# FE_Channel.net
KiCad netlist of a schematic drawn in Altium Designer
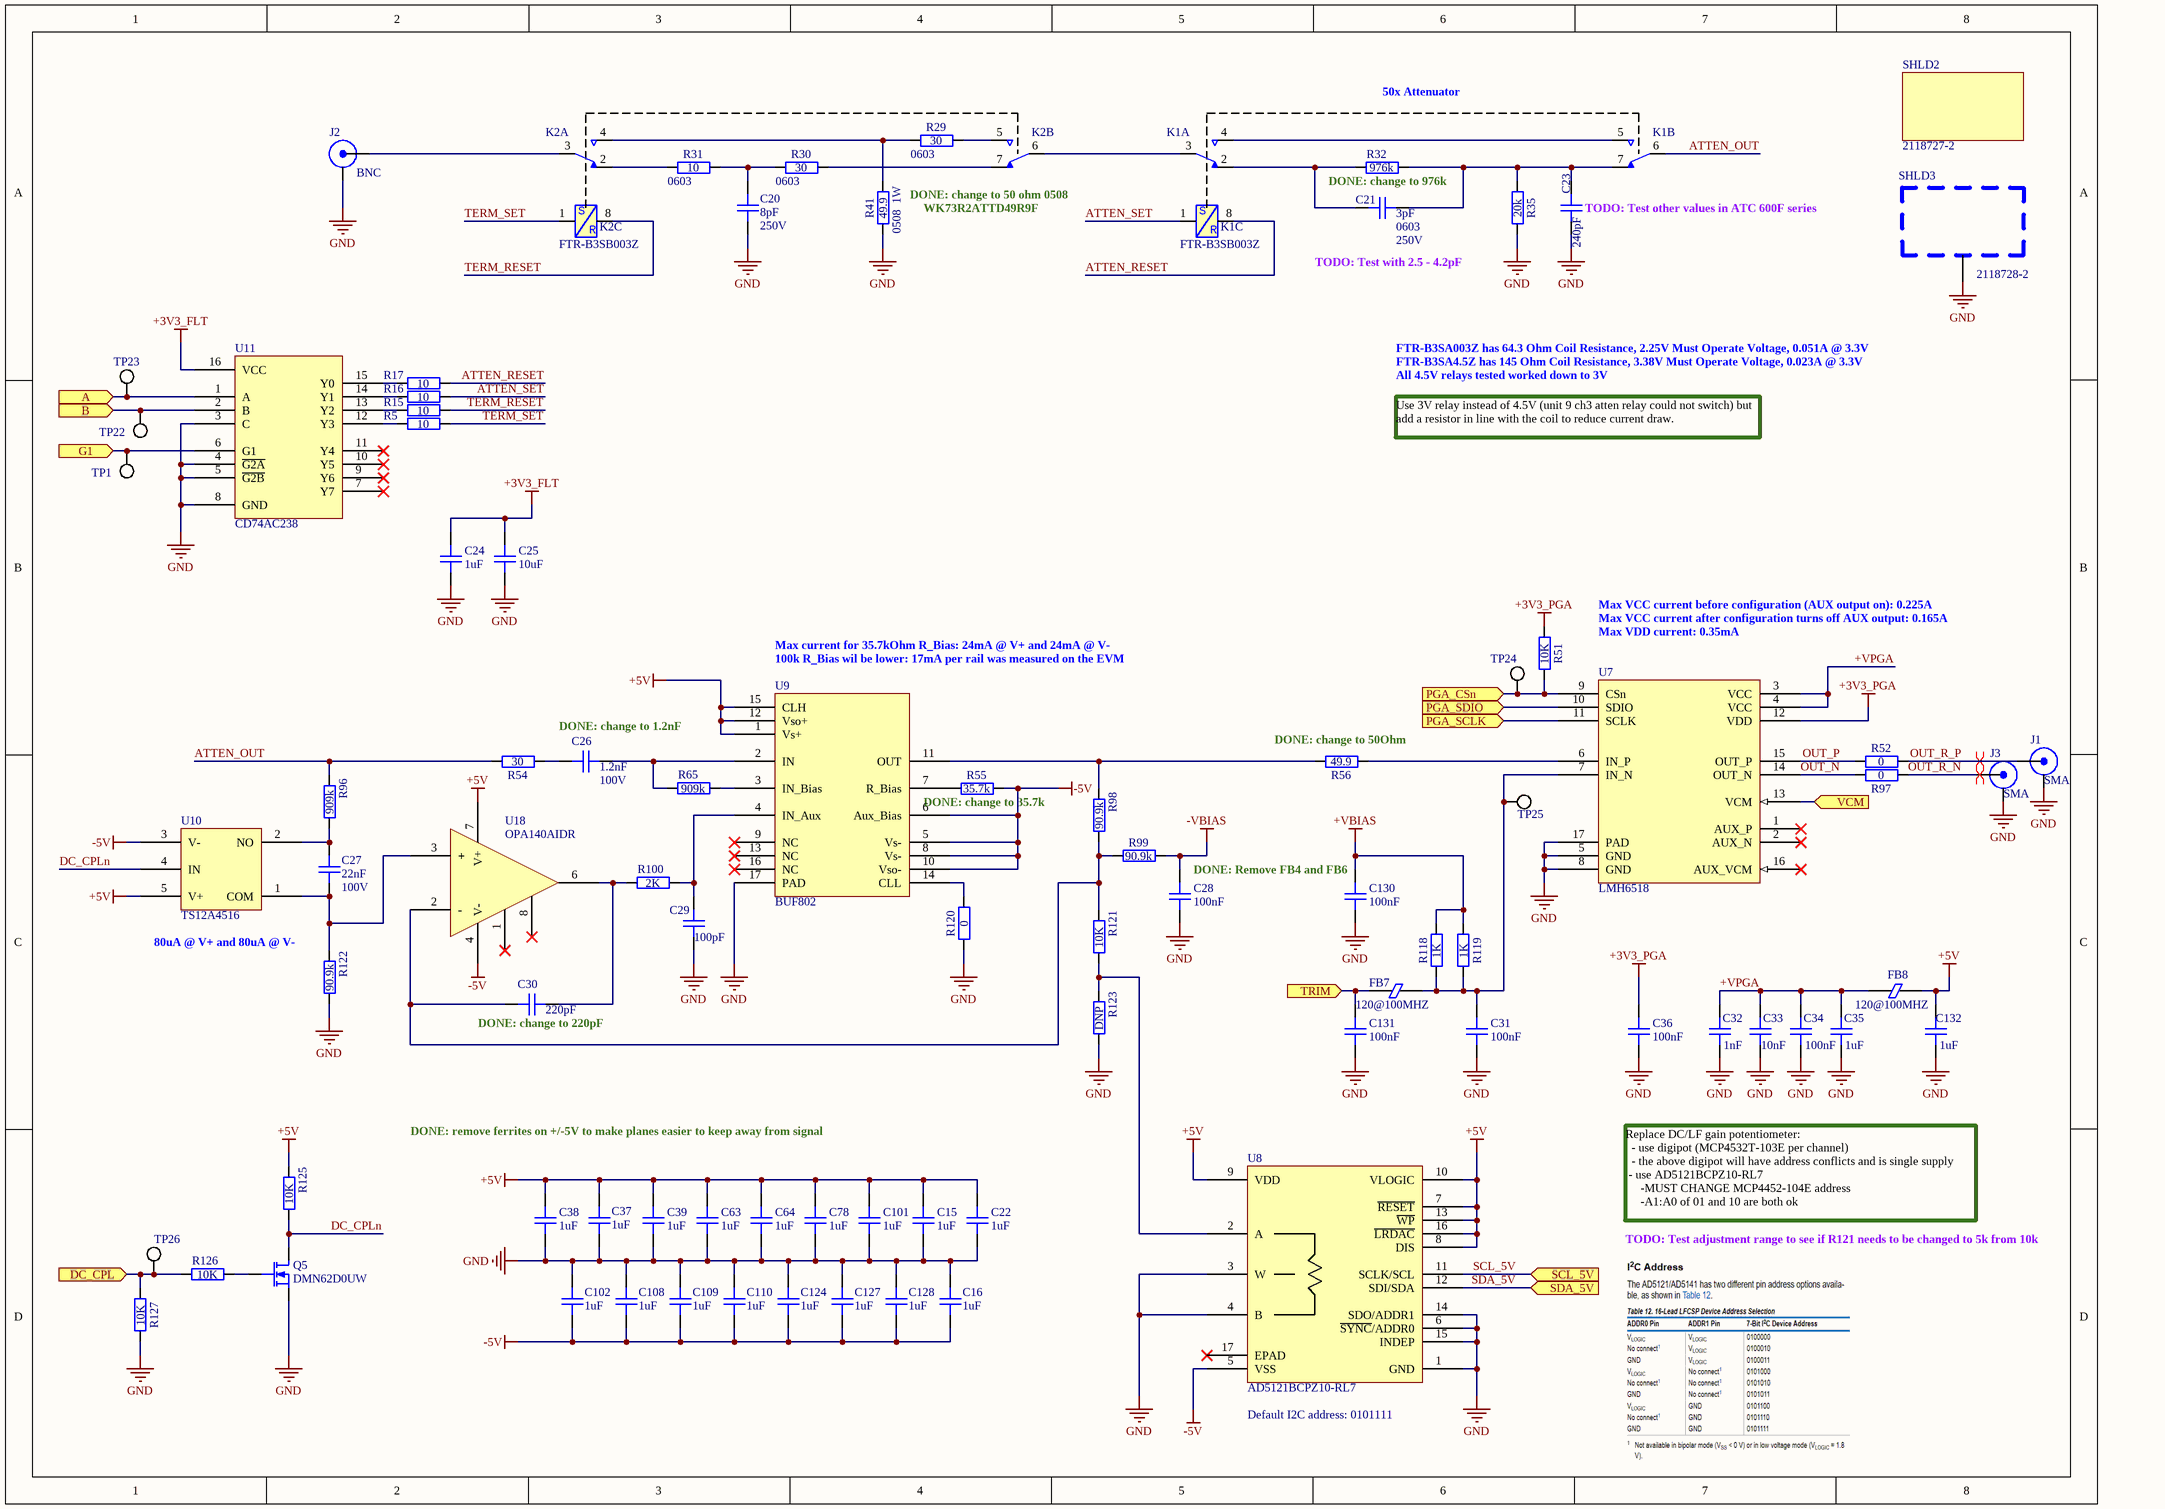
[diagram p0: FE_Channel.SchDoc]

(export (version "E")
  (design (tool "Eeschema 10.0.6"))
  (components
    (comp (ref "C15")
      (value "1uF")
      (footprint "GEN_C_0402")
      (fields
        (field (name "MANUFACTURER") "Murata")
        (field (name "MANUFACTURER PART NUMBER") "GRM155R61E105KA12D")
      )
      (libsource (lib "DSO") (part "CAP 1uF 25V X5R 0402"))
    )
    (comp (ref "C16")
      (value "1uF")
      (footprint "GEN_C_0402")
      (fields
        (field (name "MANUFACTURER") "Murata")
        (field (name "MANUFACTURER PART NUMBER") "GRM155R61E105KA12D")
      )
      (libsource (lib "DSO") (part "CAP 1uF 25V X5R 0402"))
    )
    (comp (ref "C20")
      (value "8pF")
      (footprint "GEN_C_0603")
      (fields
        (field (name "MANUFACTURER") "KEMET")
        (field (name "MANUFACTURER PART NUMBER") "CBR06C809BAGAC")
        (field (name "VOLTAGE RATING") "250V")
      )
      (libsource (lib "DSO") (part "CAP 8pF 250V C0G 0603"))
    )
    (comp (ref "C21")
      (value "3pF")
      (footprint "GEN_C_0603")
      (fields
        (field (name "PACKAGE") "0603")
        (field (name "VOLTAGE RATING") "250V")
        (field (name "MANUFACTURER") "KEMET")
        (field (name "MANUFACTURER PART NUMBER") "CBR06C309BAGAC")
      )
      (libsource (lib "DSO") (part "CAP 3pF 250V C0G 0603"))
    )
    (comp (ref "C22")
      (value "1uF")
      (footprint "GEN_C_0402")
      (fields
        (field (name "MANUFACTURER") "Murata")
        (field (name "MANUFACTURER PART NUMBER") "GRM155R61E105KA12D")
      )
      (libsource (lib "DSO") (part "CAP 1uF 25V X5R 0402"))
    )
    (comp (ref "C23")
      (value "240pF")
      (footprint "GEN_C_0805")
      (fields
        (field (name "MANUFACTURER") "Kyocera AVX")
        (field (name "MANUFACTURER PART NUMBER") "600F241FT250XT")
      )
      (libsource (lib "DSO") (part "CAP 240pF 250V C0G 0805"))
    )
    (comp (ref "C24")
      (value "1uF")
      (footprint "GEN_C_0402")
      (fields
        (field (name "MANUFACTURER") "Murata")
        (field (name "MANUFACTURER PART NUMBER") "GRM155R61E105KA12D")
      )
      (libsource (lib "DSO") (part "CAP 1uF 25V X5R 0402"))
    )
    (comp (ref "C25")
      (value "10uF")
      (footprint "GEN_C_0603")
      (fields
        (field (name "HOUSE PART NUMBER") "C-10uF-0603-002")
        (field (name "MANUFACTURER") "Murata")
        (field (name "MANUFACTURER PART NUMBER") "GRM188R61A106ME69D")
      )
      (libsource (lib "DSO") (part "CAP 10uF 10V X5R 0603"))
    )
    (comp (ref "C26")
      (value "1.2nF")
      (footprint "GEN_C_0603")
      (fields
        (field (name "VOLTAGE RATING") "100V")
        (field (name "MANUFACTURER") "Murata")
        (field (name "MANUFACTURER PART NUMBER") "GCM1885C2A122FA16D")
      )
      (libsource (lib "DSO") (part "CAP 1.2nF 100V C0G 0603"))
    )
    (comp (ref "C27")
      (value "22nF")
      (footprint "GEN_C_0603")
      (fields
        (field (name "VOLTAGE RATING") "100V")
        (field (name "MANUFACTURER") "Murata")
        (field (name "MANUFACTURER PART NUMBER") "GCM188R72A223KA37D")
      )
      (libsource (lib "DSO") (part "CAP 22nF 100V X7R 0603"))
    )
    (comp (ref "C28")
      (value "100nF")
      (footprint "GEN_C_0402")
      (fields
        (field (name "HOUSE PART NUMBER") "C-100nF-0402-002")
        (field (name "MANUFACTURER") "Murata")
        (field (name "MANUFACTURER PART NUMBER") "GCM155R71C104KA55D")
      )
      (libsource (lib "DSO") (part "CAP 100nF 16V X7R 0402"))
    )
    (comp (ref "C29")
      (value "100pF")
      (footprint "GEN_C_0402")
      (fields
        (field (name "MANUFACTURER") "Murata")
        (field (name "MANUFACTURER PART NUMBER") "GCM1555C1H101FA16D")
      )
      (libsource (lib "DSO") (part "CAP 100pF 50V C0G 0402"))
    )
    (comp (ref "C30")
      (value "220pF")
      (footprint "GEN_C_0402")
      (fields
        (field (name "MANUFACTURER") "Murata")
        (field (name "MANUFACTURER PART NUMBER") "GCM1555C1H221FA16J")
      )
      (libsource (lib "DSO") (part "CAP 220pF 50V C0G 0402"))
    )
    (comp (ref "C31")
      (value "100nF")
      (footprint "GEN_C_0402")
      (fields
        (field (name "HOUSE PART NUMBER") "C-100nF-0402-002")
        (field (name "MANUFACTURER") "Murata")
        (field (name "MANUFACTURER PART NUMBER") "GCM155R71C104KA55D")
      )
      (libsource (lib "DSO") (part "CAP 100nF 16V X7R 0402"))
    )
    (comp (ref "C32")
      (value "1nF")
      (footprint "GEN_C_0402")
      (fields
        (field (name "MANUFACTURER") "Murata")
        (field (name "MANUFACTURER PART NUMBER") "GRM1555C1H102FA01D")
      )
      (libsource (lib "DSO") (part "CAP 1nF 50V C0G 0402"))
    )
    (comp (ref "C33")
      (value "10nF")
      (footprint "GEN_C_0402")
      (fields
        (field (name "HOUSE PART NUMBER") "C-10nF-0402-002")
        (field (name "MANUFACTURER") "Murata")
        (field (name "MANUFACTURER PART NUMBER") "GRM155R71H103KA88J")
      )
      (libsource (lib "DSO") (part "CAP 10nF 50V X7R 0402"))
    )
    (comp (ref "C34")
      (value "100nF")
      (footprint "GEN_C_0402")
      (fields
        (field (name "HOUSE PART NUMBER") "C-100nF-0402-002")
        (field (name "MANUFACTURER") "Murata")
        (field (name "MANUFACTURER PART NUMBER") "GCM155R71C104KA55D")
      )
      (libsource (lib "DSO") (part "CAP 100nF 16V X7R 0402"))
    )
    (comp (ref "C35")
      (value "1uF")
      (footprint "GEN_C_0402")
      (fields
        (field (name "MANUFACTURER") "Murata")
        (field (name "MANUFACTURER PART NUMBER") "GRM155R61E105KA12D")
      )
      (libsource (lib "DSO") (part "CAP 1uF 25V X5R 0402"))
    )
    (comp (ref "C36")
      (value "100nF")
      (footprint "GEN_C_0402")
      (fields
        (field (name "HOUSE PART NUMBER") "C-100nF-0402-002")
        (field (name "MANUFACTURER") "Murata")
        (field (name "MANUFACTURER PART NUMBER") "GCM155R71C104KA55D")
      )
      (libsource (lib "DSO") (part "CAP 100nF 16V X7R 0402"))
    )
    (comp (ref "C37")
      (value "1uF")
      (footprint "GEN_C_0402")
      (fields
        (field (name "MANUFACTURER") "Murata")
        (field (name "MANUFACTURER PART NUMBER") "GRM155R61E105KA12D")
      )
      (libsource (lib "DSO") (part "CAP 1uF 25V X5R 0402"))
    )
    (comp (ref "C38")
      (value "1uF")
      (footprint "GEN_C_0402")
      (fields
        (field (name "MANUFACTURER") "Murata")
        (field (name "MANUFACTURER PART NUMBER") "GRM155R61E105KA12D")
      )
      (libsource (lib "DSO") (part "CAP 1uF 25V X5R 0402"))
    )
    (comp (ref "C39")
      (value "1uF")
      (footprint "GEN_C_0402")
      (fields
        (field (name "MANUFACTURER") "Murata")
        (field (name "MANUFACTURER PART NUMBER") "GRM155R61E105KA12D")
      )
      (libsource (lib "DSO") (part "CAP 1uF 25V X5R 0402"))
    )
    (comp (ref "C63")
      (value "1uF")
      (footprint "GEN_C_0402")
      (fields
        (field (name "MANUFACTURER") "Murata")
        (field (name "MANUFACTURER PART NUMBER") "GRM155R61E105KA12D")
      )
      (libsource (lib "DSO") (part "CAP 1uF 25V X5R 0402"))
    )
    (comp (ref "C64")
      (value "1uF")
      (footprint "GEN_C_0402")
      (fields
        (field (name "MANUFACTURER") "Murata")
        (field (name "MANUFACTURER PART NUMBER") "GRM155R61E105KA12D")
      )
      (libsource (lib "DSO") (part "CAP 1uF 25V X5R 0402"))
    )
    (comp (ref "C78")
      (value "1uF")
      (footprint "GEN_C_0402")
      (fields
        (field (name "MANUFACTURER") "Murata")
        (field (name "MANUFACTURER PART NUMBER") "GRM155R61E105KA12D")
      )
      (libsource (lib "DSO") (part "CAP 1uF 25V X5R 0402"))
    )
    (comp (ref "C101")
      (value "1uF")
      (footprint "GEN_C_0402")
      (fields
        (field (name "MANUFACTURER") "Murata")
        (field (name "MANUFACTURER PART NUMBER") "GRM155R61E105KA12D")
      )
      (libsource (lib "DSO") (part "CAP 1uF 25V X5R 0402"))
    )
    (comp (ref "C102")
      (value "1uF")
      (footprint "GEN_C_0402")
      (fields
        (field (name "MANUFACTURER") "Murata")
        (field (name "MANUFACTURER PART NUMBER") "GRM155R61E105KA12D")
      )
      (libsource (lib "DSO") (part "CAP 1uF 25V X5R 0402"))
    )
    (comp (ref "C108")
      (value "1uF")
      (footprint "GEN_C_0402")
      (fields
        (field (name "MANUFACTURER") "Murata")
        (field (name "MANUFACTURER PART NUMBER") "GRM155R61E105KA12D")
      )
      (libsource (lib "DSO") (part "CAP 1uF 25V X5R 0402"))
    )
    (comp (ref "C109")
      (value "1uF")
      (footprint "GEN_C_0402")
      (fields
        (field (name "MANUFACTURER") "Murata")
        (field (name "MANUFACTURER PART NUMBER") "GRM155R61E105KA12D")
      )
      (libsource (lib "DSO") (part "CAP 1uF 25V X5R 0402"))
    )
    (comp (ref "C110")
      (value "1uF")
      (footprint "GEN_C_0402")
      (fields
        (field (name "MANUFACTURER") "Murata")
        (field (name "MANUFACTURER PART NUMBER") "GRM155R61E105KA12D")
      )
      (libsource (lib "DSO") (part "CAP 1uF 25V X5R 0402"))
    )
    (comp (ref "C124")
      (value "1uF")
      (footprint "GEN_C_0402")
      (fields
        (field (name "MANUFACTURER") "Murata")
        (field (name "MANUFACTURER PART NUMBER") "GRM155R61E105KA12D")
      )
      (libsource (lib "DSO") (part "CAP 1uF 25V X5R 0402"))
    )
    (comp (ref "C127")
      (value "1uF")
      (footprint "GEN_C_0402")
      (fields
        (field (name "MANUFACTURER") "Murata")
        (field (name "MANUFACTURER PART NUMBER") "GRM155R61E105KA12D")
      )
      (libsource (lib "DSO") (part "CAP 1uF 25V X5R 0402"))
    )
    (comp (ref "C128")
      (value "1uF")
      (footprint "GEN_C_0402")
      (fields
        (field (name "MANUFACTURER") "Murata")
        (field (name "MANUFACTURER PART NUMBER") "GRM155R61E105KA12D")
      )
      (libsource (lib "DSO") (part "CAP 1uF 25V X5R 0402"))
    )
    (comp (ref "C130")
      (value "100nF")
      (footprint "GEN_C_0402")
      (fields
        (field (name "HOUSE PART NUMBER") "C-100nF-0402-002")
        (field (name "MANUFACTURER") "Murata")
        (field (name "MANUFACTURER PART NUMBER") "GCM155R71C104KA55D")
      )
      (libsource (lib "DSO") (part "CAP 100nF 16V X7R 0402"))
    )
    (comp (ref "C131")
      (value "100nF")
      (footprint "GEN_C_0402")
      (fields
        (field (name "HOUSE PART NUMBER") "C-100nF-0402-002")
        (field (name "MANUFACTURER") "Murata")
        (field (name "MANUFACTURER PART NUMBER") "GCM155R71C104KA55D")
      )
      (libsource (lib "DSO") (part "CAP 100nF 16V X7R 0402"))
    )
    (comp (ref "C132")
      (value "1uF")
      (footprint "GEN_C_0402")
      (fields
        (field (name "MANUFACTURER") "Murata")
        (field (name "MANUFACTURER PART NUMBER") "GRM155R61E105KA12D")
      )
      (libsource (lib "DSO") (part "CAP 1uF 25V X5R 0402"))
    )
    (comp (ref "FB7")
      (value "120@100MHZ")
      (footprint "GEN_R_0402")
      (fields (field (name "HOUSE PART NUMBER") "BLM15PX121SN1D") (field (name "MANUFACTURER") "Murata"))
      (libsource (lib "DSO") (part "FERRITE BEAD 120 OHM 0402"))
    )
    (comp (ref "FB8")
      (value "120@100MHZ")
      (footprint "GEN_R_0402")
      (fields (field (name "HOUSE PART NUMBER") "BLM15PX121SN1D") (field (name "MANUFACTURER") "Murata"))
      (libsource (lib "DSO") (part "FERRITE BEAD 120 OHM 0402"))
    )
    (comp (ref "J1")
      (value "SMA")
      (footprint "MOL_0733910083")
      (fields (field (name "MANUFACTURER") "Molex") (field (name "MANUFACTURER PART NUMBER") "73100-0105"))
      (libsource (lib "DSO") (part "SMA JACK R/A"))
    )
    (comp (ref "J2")
      (value "BNC")
      (footprint "MOL_0731000105")
      (fields (field (name "MANUFACTURER") "Molex") (field (name "MANUFACTURER PART NUMBER") "73100-0105"))
      (libsource (lib "DSO") (part "BNC JACK R/A"))
    )
    (comp (ref "J3")
      (value "SMA")
      (footprint "MOL_0733910083")
      (fields (field (name "MANUFACTURER") "Molex") (field (name "MANUFACTURER PART NUMBER") "73100-0105"))
      (libsource (lib "DSO") (part "SMA JACK R/A"))
    )
    (comp (ref "K1")
      (value "FTR-B3SB003Z")
      (footprint "FUJ_FTR-B3SA")
      (fields (field (name "MANUFACTURER") "Fujitsu"))
      (libsource (lib "") (part "RELAY DPDT-NO FTR-B3SB003Z_1"))
    )
    (comp (ref "K2")
      (value "FTR-B3SB003Z")
      (footprint "FUJ_FTR-B3SA")
      (fields (field (name "MANUFACTURER") "Fujitsu"))
      (libsource (lib "DSO") (part "RELAY DPDT-NO FTR-B3SB003Z"))
    )
    (comp (ref "Q5")
      (value "DMN62D0UW")
      (footprint "GEN_SOT_323")
      (fields (field (name "HOUSE PART NUMBER") "DMN62D0UW-7") (field (name "MANUFACTURER") "Diodes"))
      (libsource (lib "DSO") (part "NMOS DMN62D0UW"))
    )
    (comp (ref "R5")
      (value "10")
      (footprint "GEN_R_0603")
      (fields
        (field (name "TOLERANCE") "1%")
        (field (name "MANUFACTURER") "KOA Speer")
        (field (name "MANUFACTURER PART NUMBER") "SG73P1JTTD10R0F")
      )
      (libsource (lib "DSO") (part "RES 10 OHM 1% 1/3W 0603"))
    )
    (comp (ref "R15")
      (value "10")
      (footprint "GEN_R_0603")
      (fields
        (field (name "TOLERANCE") "1%")
        (field (name "MANUFACTURER") "KOA Speer")
        (field (name "MANUFACTURER PART NUMBER") "SG73P1JTTD10R0F")
      )
      (libsource (lib "DSO") (part "RES 10 OHM 1% 1/3W 0603"))
    )
    (comp (ref "R16")
      (value "10")
      (footprint "GEN_R_0603")
      (fields
        (field (name "TOLERANCE") "1%")
        (field (name "MANUFACTURER") "KOA Speer")
        (field (name "MANUFACTURER PART NUMBER") "SG73P1JTTD10R0F")
      )
      (libsource (lib "DSO") (part "RES 10 OHM 1% 1/3W 0603"))
    )
    (comp (ref "R17")
      (value "10")
      (footprint "GEN_R_0603")
      (fields
        (field (name "TOLERANCE") "1%")
        (field (name "MANUFACTURER") "KOA Speer")
        (field (name "MANUFACTURER PART NUMBER") "SG73P1JTTD10R0F")
      )
      (libsource (lib "DSO") (part "RES 10 OHM 1% 1/3W 0603"))
    )
    (comp (ref "R29")
      (value "30")
      (footprint "GEN_R_0603")
      (fields
        (field (name "TOLERANCE") "1%")
        (field (name "PACKAGE") "0603")
        (field (name "MANUFACTURER") "KOA Speer")
        (field (name "MANUFACTURER PART NUMBER") "SG73P1JTTD30R0F")
      )
      (libsource (lib "DSO") (part "RES 30 OHM 1% 1/3W 0603"))
    )
    (comp (ref "R30")
      (value "30")
      (footprint "GEN_R_0603")
      (fields
        (field (name "TOLERANCE") "1%")
        (field (name "PACKAGE") "0603")
        (field (name "MANUFACTURER") "KOA Speer")
        (field (name "MANUFACTURER PART NUMBER") "SG73P1JTTD30R0F")
      )
      (libsource (lib "DSO") (part "RES 30 OHM 1% 1/3W 0603"))
    )
    (comp (ref "R31")
      (value "10")
      (footprint "GEN_R_0603")
      (fields
        (field (name "TOLERANCE") "1%")
        (field (name "PACKAGE") "0603")
        (field (name "MANUFACTURER") "KOA Speer")
        (field (name "MANUFACTURER PART NUMBER") "SG73P1JTTD10R0F")
      )
      (libsource (lib "") (part "RES 10 OHM 1% 1/3W 0603_1"))
    )
    (comp (ref "R32")
      (value "976k")
      (footprint "GEN_R_0603")
      (fields
        (field (name "MANUFACTURER") "KOA Speer")
        (field (name "MANUFACTURER PART NUMBER") "RK73H1JTTD9763F")
        (field (name "TOLERANCE") "1%")
      )
      (libsource (lib "DSO") (part "RES 976k OHM 1% 1/10W 0603"))
    )
    (comp (ref "R35")
      (value "20k")
      (footprint "GEN_R_0402")
      (fields
        (field (name "TOLERANCE") "1%")
        (field (name "MANUFACTURER") "Yageo")
        (field (name "MANUFACTURER PART NUMBER") "RC0402FR-0720KL")
      )
      (libsource (lib "DSO") (part "RES 20K OHM 1% 1/16W 0402"))
    )
    (comp (ref "R41")
      (value "49.9")
      (footprint "GEN_R_0508")
      (fields
        (field (name "TOLERANCE") "1%")
        (field (name "PACKAGE") "0508")
        (field (name "MANUFACTURER") "KOA Speer")
        (field (name "MANUFACTURER PART NUMBER") "WK73R2ATTD49R9F")
        (field (name "POWER RATING") "1W")
      )
      (libsource (lib "DSO") (part "RES 49.9 OHM 1% 1W 0508"))
    )
    (comp (ref "R51")
      (value "10K")
      (footprint "GEN_R_0402")
      (fields
        (field (name "TOLERANCE") "1%")
        (field (name "MANUFACTURER") "Panasonic")
        (field (name "MANUFACTURER PART NUMBER") "ERJ-2RKF1002X")
      )
      (libsource (lib "DSO") (part "RES 10K OHM 1% 1/10W 0402"))
    )
    (comp (ref "R52")
      (value "0")
      (footprint "GEN_R_0402")
      (fields
        (field (name "MANUFACTURER") "Yageo")
        (field (name "MANUFACTURER PART NUMBER") "RC0402JR-070RL")
      )
      (libsource (lib "DSO") (part "RES 0 OHM 1/16W 0402"))
    )
    (comp (ref "R54")
      (value "30")
      (footprint "GEN_R_0603")
      (fields
        (field (name "TOLERANCE") "1%")
        (field (name "MANUFACTURER") "KOA Speer")
        (field (name "MANUFACTURER PART NUMBER") "SG73P1JTTD30R0F")
      )
      (libsource (lib "DSO") (part "RES 30 OHM 1% 1/3W 0603"))
    )
    (comp (ref "R55")
      (value "35.7k")
      (footprint "GEN_R_0402")
      (fields
        (field (name "TOLERANCE") "1%")
        (field (name "MANUFACTURER") "Yageo")
        (field (name "MANUFACTURER PART NUMBER") "RC0402FR-0735K7L")
      )
      (libsource (lib "DSO") (part "RES 35.7K OHM 1% 1/16W 0402"))
    )
    (comp (ref "R56")
      (value "49.9")
      (footprint "GEN_R_0402")
      (fields
        (field (name "MANUFACTURER") "Yageo")
        (field (name "MANUFACTURER PART NUMBER") "RC0402FR-0749R9L")
        (field (name "TOLERANCE") "1%")
      )
      (libsource (lib "DSO") (part "RES 49.9 OHM 1% 1/10W 0402"))
    )
    (comp (ref "R65")
      (value "909k")
      (footprint "GEN_R_0402")
      (fields
        (field (name "TOLERANCE") "1%")
        (field (name "MANUFACTURER") "Yageo")
        (field (name "MANUFACTURER PART NUMBER") "RC0402FR-07909KL")
      )
      (libsource (lib "DSO") (part "RES 909K OHM 1% 1/16W 0402"))
    )
    (comp (ref "R96")
      (value "909k")
      (footprint "GEN_R_0402")
      (fields
        (field (name "TOLERANCE") "1%")
        (field (name "MANUFACTURER") "Yageo")
        (field (name "MANUFACTURER PART NUMBER") "RC0402FR-07909KL")
      )
      (libsource (lib "") (part "RES 909K OHM 1% 1/16W 0402_1"))
    )
    (comp (ref "R97")
      (value "0")
      (footprint "GEN_R_0402")
      (fields
        (field (name "MANUFACTURER") "Yageo")
        (field (name "MANUFACTURER PART NUMBER") "RC0402JR-070RL")
      )
      (libsource (lib "DSO") (part "RES 0 OHM 1/16W 0402"))
    )
    (comp (ref "R98")
      (value "90.9k")
      (footprint "GEN_R_0402")
      (fields
        (field (name "TOLERANCE") "1%")
        (field (name "MANUFACTURER") "Yageo")
        (field (name "MANUFACTURER PART NUMBER") "RC0402FR-0790K9L")
      )
      (libsource (lib "DSO") (part "RES 90.9K OHM 1% 1/16W 0402"))
    )
    (comp (ref "R99")
      (value "90.9k")
      (footprint "GEN_R_0402")
      (fields
        (field (name "TOLERANCE") "1%")
        (field (name "MANUFACTURER") "Yageo")
        (field (name "MANUFACTURER PART NUMBER") "RC0402FR-0790K9L")
      )
      (libsource (lib "") (part "RES 90.9K OHM 1% 1/16W 0402_1"))
    )
    (comp (ref "R100")
      (value "2K")
      (footprint "GEN_R_0402")
      (fields
        (field (name "TOLERANCE") "1%")
        (field (name "MANUFACTURER") "Yageo")
        (field (name "MANUFACTURER PART NUMBER") "RC0402FR-072KL")
      )
      (libsource (lib "DSO") (part "RES 2K OHM 1% 1/16W 0402"))
    )
    (comp (ref "R118")
      (value "1K")
      (footprint "GEN_R_0402")
      (fields
        (field (name "TOLERANCE") "1%")
        (field (name "HOUSE PART NUMBER") "R-1K-0402-1%-001")
        (field (name "MANUFACTURER") "Yageo")
      )
      (libsource (lib "DSO") (part "RES 1K OHM 1% 1/10W 0402"))
    )
    (comp (ref "R119")
      (value "1K")
      (footprint "GEN_R_0402")
      (fields
        (field (name "TOLERANCE") "1%")
        (field (name "HOUSE PART NUMBER") "R-1K-0402-1%-001")
        (field (name "MANUFACTURER") "Yageo")
      )
      (libsource (lib "") (part "RES 1K OHM 1% 1/10W 0402_1"))
    )
    (comp (ref "R120")
      (value "0")
      (footprint "GEN_R_0402")
      (fields
        (field (name "MANUFACTURER") "Yageo")
        (field (name "MANUFACTURER PART NUMBER") "RC0402JR-070RL")
      )
      (libsource (lib "") (part "RES 0 OHM 1/16W 0402_1"))
    )
    (comp (ref "R121")
      (value "10K")
      (footprint "GEN_R_0402")
      (fields
        (field (name "TOLERANCE") "1%")
        (field (name "MANUFACTURER") "Panasonic")
        (field (name "MANUFACTURER PART NUMBER") "ERJ-2RKF1002X")
      )
      (libsource (lib "DSO") (part "RES 10K OHM 1% 1/10W 0402"))
    )
    (comp (ref "R122")
      (value "90.9k")
      (footprint "GEN_R_0402")
      (fields
        (field (name "TOLERANCE") "1%")
        (field (name "MANUFACTURER") "Yageo")
        (field (name "MANUFACTURER PART NUMBER") "RC0402FR-0790K9L")
      )
      (libsource (lib "DSO") (part "RES 90.9K OHM 1% 1/16W 0402"))
    )
    (comp (ref "R123")
      (value "DNP")
      (footprint "GEN_R_0402")
      (fields (field (name "TOLERANCE") "1%"))
      (libsource (lib "DSO") (part "RES DNP 0402"))
    )
    (comp (ref "R125")
      (value "10K")
      (footprint "GEN_R_0402")
      (fields
        (field (name "TOLERANCE") "1%")
        (field (name "MANUFACTURER") "Panasonic")
        (field (name "MANUFACTURER PART NUMBER") "ERJ-2RKF1002X")
      )
      (libsource (lib "DSO") (part "RES 10K OHM 1% 1/10W 0402"))
    )
    (comp (ref "R126")
      (value "10K")
      (footprint "GEN_R_0402")
      (fields
        (field (name "TOLERANCE") "1%")
        (field (name "MANUFACTURER") "Panasonic")
        (field (name "MANUFACTURER PART NUMBER") "ERJ-2RKF1002X")
      )
      (libsource (lib "") (part "RES 10K OHM 1% 1/10W 0402_1"))
    )
    (comp (ref "R127")
      (value "10K")
      (footprint "GEN_R_0402")
      (fields
        (field (name "TOLERANCE") "1%")
        (field (name "MANUFACTURER") "Panasonic")
        (field (name "MANUFACTURER PART NUMBER") "ERJ-2RKF1002X")
      )
      (libsource (lib "") (part "RES 10K OHM 1% 1/10W 0402_2"))
    )
    (comp (ref "SHLD2")
      (value "2118727-2")
      (fields (field (name "MANUFACTURER") "TE Connectivity AMP"))
      (libsource (lib "DSO") (part "SHIELD 2118727-2"))
    )
    (comp (ref "SHLD3")
      (value "2118728-2")
      (footprint "TE_2118728-2")
      (fields (field (name "MANUFACTURER") "TE Connectivity"))
      (libsource (lib "DSO") (part "SHIELD 2118728-2"))
    )
    (comp (ref "TP1") (value "PCB") (footprint "GEN_TP_PCB") (libsource (lib "DSO") (part "TP PCB 1mm")))
    (comp (ref "TP22") (value "PCB") (footprint "GEN_TP_PCB") (libsource (lib "DSO") (part "TP PCB 1mm")))
    (comp (ref "TP23") (value "PCB") (footprint "GEN_TP_PCB") (libsource (lib "DSO") (part "TP PCB 1mm")))
    (comp (ref "TP24") (value "PCB") (footprint "GEN_TP_PCB") (libsource (lib "DSO") (part "TP PCB 1mm")))
    (comp (ref "TP25") (value "PCB") (footprint "GEN_TP_PCB") (libsource (lib "DSO") (part "TP PCB 1mm")))
    (comp (ref "TP26") (value "PCB") (footprint "GEN_TP_PCB") (libsource (lib "DSO") (part "TP PCB 1mm")))
    (comp (ref "U7")
      (value "LMH6518")
      (footprint "TI_WQFN_RGH0016A")
      (fields
        (field (name "MANUFACTURER") "Texas Instruments")
        (field (name "MANUFACTURER PART NUMBER") "LMH6518SQE/NOPB")
      )
      (libsource (lib "DSO") (part "IC PGA LMH6518"))
    )
    (comp (ref "U8")
      (value "AD5121BCPZ10-RL7")
      (footprint "AD_QFN16_CP-16-22")
      (fields (field (name "MANUFACTURER") "Analog Devices"))
      (libsource (lib "DSO") (part "IC DIGIPOT SINGLE AD5121BCPZ10-RL7"))
    )
    (comp (ref "U9")
      (value "BUF802")
      (footprint "TI_VQFN_RGT0016C")
      (fields
        (field (name "MANUFACTURER") "Texas Instruments")
        (field (name "MANUFACTURER PART NUMBER") "BUF802IRGTR")
      )
      (libsource (lib "DSO") (part "IC BUFFER AMP BUF802"))
    )
    (comp (ref "U10")
      (value "TS12A4516")
      (footprint "GEN_SOT23_5_950_2900X1600X1450")
      (fields
        (field (name "MANUFACTURER") "Texas Instruments")
        (field (name "MANUFACTURER PART NUMBER") "TS12A4516DBVR")
      )
      (libsource (lib "DSO") (part "IC SWITCH SPST TS12A4516DBVR"))
    )
    (comp (ref "U11")
      (value "CD74AC238")
      (footprint "TI_TSSOP16_PW0016A")
      (fields
        (field (name "MANUFACTURER") "Texas Instruments")
        (field (name "HOUSE PART NUMBER") "CD74AC238PWR")
      )
      (libsource (lib "DSO") (part "IC Decoder CD74AC238"))
    )
    (comp (ref "U18")
      (value "OPA140AIDR")
      (footprint "TI_SOIC8_D0008A")
      (fields (field (name "MANUFACTURER") "Texas Instruments"))
      (libsource (lib "DSO") (part "IC OPAMP OPA140"))
    )
  )
  (nets
    (net (code "1") (name "+3V3_FLT") (class "Default")
      (node (ref "C24") (pin "2") (pinfunction "2_2") (pintype "passive"))
      (node (ref "C25") (pin "2") (pinfunction "2_2") (pintype "passive"))
      (node (ref "U11") (pin "16") (pinfunction "VCC_16") (pintype "passive"))
    )
    (net (code "2") (name "+3V3_PGA") (class "Default")
      (node (ref "C36") (pin "2") (pinfunction "2_2") (pintype "passive"))
      (node (ref "R51") (pin "2") (pinfunction "2_2") (pintype "passive"))
      (node (ref "U7") (pin "12") (pinfunction "VDD_12") (pintype "power_in"))
    )
    (net (code "3") (name "+5V") (class "Default")
      (node (ref "C101") (pin "2") (pinfunction "2_2") (pintype "passive"))
      (node (ref "C132") (pin "2") (pinfunction "2_2") (pintype "passive"))
      (node (ref "C15") (pin "2") (pinfunction "2_2") (pintype "passive"))
      (node (ref "C22") (pin "2") (pinfunction "2_2") (pintype "passive"))
      (node (ref "C37") (pin "2") (pinfunction "2_2") (pintype "passive"))
      (node (ref "C38") (pin "1") (pinfunction "1_1") (pintype "passive"))
      (node (ref "C39") (pin "1") (pinfunction "1_1") (pintype "passive"))
      (node (ref "C63") (pin "1") (pinfunction "1_1") (pintype "passive"))
      (node (ref "C64") (pin "2") (pinfunction "2_2") (pintype "passive"))
      (node (ref "C78") (pin "2") (pinfunction "2_2") (pintype "passive"))
      (node (ref "FB8") (pin "2") (pinfunction "2_2") (pintype "passive"))
      (node (ref "R125") (pin "2") (pinfunction "2_2") (pintype "passive"))
      (node (ref "U10") (pin "5") (pinfunction "V+_5") (pintype "passive"))
      (node (ref "U18") (pin "7") (pinfunction "V+_7") (pintype "passive"))
      (node (ref "U8") (pin "10") (pinfunction "VLOGIC_10") (pintype "passive"))
      (node (ref "U8") (pin "13") (pinfunction "~{WP}_13") (pintype "passive"))
      (node (ref "U8") (pin "16") (pinfunction "~{LRDAC}_16") (pintype "passive"))
      (node (ref "U8") (pin "7") (pinfunction "~{RESET}_7") (pintype "passive"))
      (node (ref "U8") (pin "8") (pinfunction "DIS_8") (pintype "passive"))
      (node (ref "U8") (pin "9") (pinfunction "VDD_9") (pintype "passive"))
      (node (ref "U9") (pin "1") (pinfunction "Vs+_1") (pintype "passive"))
      (node (ref "U9") (pin "12") (pinfunction "Vso+_12") (pintype "passive"))
      (node (ref "U9") (pin "15") (pinfunction "CLH_15") (pintype "passive"))
    )
    (net (code "4") (name "+VBIAS") (class "Default")
      (node (ref "C130") (pin "1") (pinfunction "1_1") (pintype "passive"))
      (node (ref "R118") (pin "2") (pinfunction "2_2") (pintype "passive"))
      (node (ref "R119") (pin "1") (pinfunction "1_1") (pintype "passive"))
    )
    (net (code "5") (name "-5V") (class "Default")
      (node (ref "C102") (pin "2") (pinfunction "2_2") (pintype "passive"))
      (node (ref "C108") (pin "2") (pinfunction "2_2") (pintype "passive"))
      (node (ref "C109") (pin "1") (pinfunction "1_1") (pintype "passive"))
      (node (ref "C110") (pin "1") (pinfunction "1_1") (pintype "passive"))
      (node (ref "C124") (pin "1") (pinfunction "1_1") (pintype "passive"))
      (node (ref "C127") (pin "2") (pinfunction "2_2") (pintype "passive"))
      (node (ref "C128") (pin "2") (pinfunction "2_2") (pintype "passive"))
      (node (ref "C16") (pin "2") (pinfunction "2_2") (pintype "passive"))
      (node (ref "R55") (pin "2") (pinfunction "2_2") (pintype "passive"))
      (node (ref "U10") (pin "3") (pinfunction "V-_3") (pintype "passive"))
      (node (ref "U18") (pin "4") (pinfunction "V-_4") (pintype "passive"))
      (node (ref "U8") (pin "5") (pinfunction "VSS_5") (pintype "passive"))
      (node (ref "U9") (pin "10") (pinfunction "Vso-_10") (pintype "passive"))
      (node (ref "U9") (pin "5") (pinfunction "Vs-_5") (pintype "passive"))
      (node (ref "U9") (pin "6") (pinfunction "Aux_Bias_6") (pintype "passive"))
      (node (ref "U9") (pin "8") (pinfunction "Vs-_8") (pintype "passive"))
    )
    (net (code "6") (name "-VBIAS") (class "Default")
      (node (ref "C28") (pin "1") (pinfunction "1_1") (pintype "passive"))
      (node (ref "R99") (pin "1") (pinfunction "1_1") (pintype "passive"))
    )
    (net (code "7") (name "/+VPGA") (class "Default")
      (node (ref "C32") (pin "2") (pinfunction "2_2") (pintype "passive"))
      (node (ref "C33") (pin "2") (pinfunction "2_2") (pintype "passive"))
      (node (ref "C34") (pin "2") (pinfunction "2_2") (pintype "passive"))
      (node (ref "C35") (pin "2") (pinfunction "2_2") (pintype "passive"))
      (node (ref "FB8") (pin "1") (pinfunction "1_1") (pintype "passive"))
      (node (ref "U7") (pin "3") (pinfunction "VCC_3") (pintype "power_in"))
      (node (ref "U7") (pin "4") (pinfunction "VCC_4") (pintype "power_in"))
    )
    (net (code "8") (name "/A") (class "Default")
      (node (ref "TP23") (pin "1") (pinfunction "1_1") (pintype "passive"))
      (node (ref "U11") (pin "1") (pinfunction "A_1") (pintype "passive"))
    )
    (net (code "9") (name "/ATTEN_OUT") (class "Default")
      (node (ref "K1") (pin "6") (pinfunction "6_6") (pintype "passive"))
      (node (ref "R54") (pin "1") (pinfunction "1_1") (pintype "passive"))
      (node (ref "R96") (pin "2") (pinfunction "2_2") (pintype "passive"))
    )
    (net (code "10") (name "/ATTEN_RESET") (class "Default")
      (node (ref "K1") (pin "8") (pinfunction "8_8") (pintype "passive"))
      (node (ref "R17") (pin "2") (pinfunction "2_2") (pintype "passive"))
    )
    (net (code "11") (name "/ATTEN_SET") (class "Default")
      (node (ref "K1") (pin "1") (pinfunction "1_1") (pintype "passive"))
      (node (ref "R16") (pin "2") (pinfunction "2_2") (pintype "passive"))
    )
    (net (code "12") (name "/B") (class "Default")
      (node (ref "TP22") (pin "1") (pinfunction "1_1") (pintype "passive"))
      (node (ref "U11") (pin "2") (pinfunction "B_2") (pintype "passive"))
    )
    (net (code "13") (name "/DC_CPL") (class "Default")
      (node (ref "R126") (pin "2") (pinfunction "2_2") (pintype "passive"))
      (node (ref "R127") (pin "2") (pinfunction "2_2") (pintype "passive"))
      (node (ref "TP26") (pin "1") (pinfunction "1_1") (pintype "passive"))
    )
    (net (code "14") (name "/DC_CPLn") (class "Default")
      (node (ref "Q5") (pin "1") (pinfunction "D_1") (pintype "passive"))
      (node (ref "R125") (pin "1") (pinfunction "1_1") (pintype "passive"))
      (node (ref "U10") (pin "4") (pinfunction "IN_4") (pintype "passive"))
    )
    (net (code "15") (name "/G1") (class "Default")
      (node (ref "TP1") (pin "1") (pinfunction "1_1") (pintype "passive"))
      (node (ref "U11") (pin "6") (pinfunction "G1_6") (pintype "passive"))
    )
    (net (code "16") (name "/OUT_N") (class "Default")
      (node (ref "R97") (pin "1") (pinfunction "1_1") (pintype "passive"))
      (node (ref "U7") (pin "14") (pinfunction "OUT_N_14") (pintype "passive"))
    )
    (net (code "17") (name "/OUT_P") (class "Default")
      (node (ref "R52") (pin "1") (pinfunction "1_1") (pintype "passive"))
      (node (ref "U7") (pin "15") (pinfunction "OUT_P_15") (pintype "passive"))
    )
    (net (code "18") (name "/OUT_R_N") (class "Default")
      (node (ref "J3") (pin "1") (pinfunction "Signal_1") (pintype "passive"))
      (node (ref "R97") (pin "2") (pinfunction "2_2") (pintype "passive"))
    )
    (net (code "19") (name "/OUT_R_P") (class "Default")
      (node (ref "J1") (pin "1") (pinfunction "Signal_1") (pintype "passive"))
      (node (ref "R52") (pin "2") (pinfunction "2_2") (pintype "passive"))
    )
    (net (code "20") (name "/PGA_CSn") (class "Default")
      (node (ref "R51") (pin "1") (pinfunction "1_1") (pintype "passive"))
      (node (ref "TP24") (pin "1") (pinfunction "1_1") (pintype "passive"))
      (node (ref "U7") (pin "9") (pinfunction "CSn_9") (pintype "passive"))
    )
    (net (code "21") (name "/PGA_SCLK") (class "Default")
      (node (ref "U7") (pin "11") (pinfunction "SCLK_11") (pintype "passive"))
    )
    (net (code "22") (name "/PGA_SDIO") (class "Default")
      (node (ref "U7") (pin "10") (pinfunction "SDIO_10") (pintype "passive"))
    )
    (net (code "23") (name "/SCL_5V") (class "Default")
      (node (ref "U8") (pin "11") (pinfunction "SCLK/SCL_11") (pintype "passive"))
    )
    (net (code "24") (name "/SDA_5V") (class "Default")
      (node (ref "U8") (pin "12") (pinfunction "SDI/SDA_12") (pintype "passive"))
    )
    (net (code "25") (name "/TERM_RESET") (class "Default")
      (node (ref "K2") (pin "8") (pinfunction "8_8") (pintype "passive"))
      (node (ref "R15") (pin "2") (pinfunction "2_2") (pintype "passive"))
    )
    (net (code "26") (name "/TERM_SET") (class "Default")
      (node (ref "K2") (pin "1") (pinfunction "1_1") (pintype "passive"))
      (node (ref "R5") (pin "2") (pinfunction "2_2") (pintype "passive"))
    )
    (net (code "27") (name "/TRIM") (class "Default")
      (node (ref "C131") (pin "1") (pinfunction "1_1") (pintype "passive"))
      (node (ref "FB7") (pin "1") (pinfunction "1_1") (pintype "passive"))
    )
    (net (code "28") (name "/VCM") (class "Default")
      (node (ref "U7") (pin "13") (pinfunction "VCM_13") (pintype "input"))
    )
    (net (code "29") (name "GND") (class "Default")
      (node (ref "C101") (pin "1") (pinfunction "1_1") (pintype "passive"))
      (node (ref "C102") (pin "1") (pinfunction "1_1") (pintype "passive"))
      (node (ref "C108") (pin "1") (pinfunction "1_1") (pintype "passive"))
      (node (ref "C109") (pin "2") (pinfunction "2_2") (pintype "passive"))
      (node (ref "C110") (pin "2") (pinfunction "2_2") (pintype "passive"))
      (node (ref "C124") (pin "2") (pinfunction "2_2") (pintype "passive"))
      (node (ref "C127") (pin "1") (pinfunction "1_1") (pintype "passive"))
      (node (ref "C128") (pin "1") (pinfunction "1_1") (pintype "passive"))
      (node (ref "C130") (pin "2") (pinfunction "2_2") (pintype "passive"))
      (node (ref "C131") (pin "2") (pinfunction "2_2") (pintype "passive"))
      (node (ref "C132") (pin "1") (pinfunction "1_1") (pintype "passive"))
      (node (ref "C15") (pin "1") (pinfunction "1_1") (pintype "passive"))
      (node (ref "C16") (pin "1") (pinfunction "1_1") (pintype "passive"))
      (node (ref "C20") (pin "2") (pinfunction "2_2") (pintype "passive"))
      (node (ref "C22") (pin "1") (pinfunction "1_1") (pintype "passive"))
      (node (ref "C23") (pin "1") (pinfunction "1_1") (pintype "passive"))
      (node (ref "C24") (pin "1") (pinfunction "1_1") (pintype "passive"))
      (node (ref "C25") (pin "1") (pinfunction "1_1") (pintype "passive"))
      (node (ref "C28") (pin "2") (pinfunction "2_2") (pintype "passive"))
      (node (ref "C29") (pin "1") (pinfunction "1_1") (pintype "passive"))
      (node (ref "C31") (pin "2") (pinfunction "2_2") (pintype "passive"))
      (node (ref "C32") (pin "1") (pinfunction "1_1") (pintype "passive"))
      (node (ref "C33") (pin "1") (pinfunction "1_1") (pintype "passive"))
      (node (ref "C34") (pin "1") (pinfunction "1_1") (pintype "passive"))
      (node (ref "C35") (pin "1") (pinfunction "1_1") (pintype "passive"))
      (node (ref "C36") (pin "1") (pinfunction "1_1") (pintype "passive"))
      (node (ref "C37") (pin "1") (pinfunction "1_1") (pintype "passive"))
      (node (ref "C38") (pin "2") (pinfunction "2_2") (pintype "passive"))
      (node (ref "C39") (pin "2") (pinfunction "2_2") (pintype "passive"))
      (node (ref "C63") (pin "2") (pinfunction "2_2") (pintype "passive"))
      (node (ref "C64") (pin "1") (pinfunction "1_1") (pintype "passive"))
      (node (ref "C78") (pin "1") (pinfunction "1_1") (pintype "passive"))
      (node (ref "J1") (pin "2") (pinfunction "SHIELD_2") (pintype "passive"))
      (node (ref "J2") (pin "2") (pinfunction "SHIELD_2") (pintype "passive"))
      (node (ref "J3") (pin "2") (pinfunction "SHIELD_2") (pintype "passive"))
      (node (ref "Q5") (pin "3") (pinfunction "S_3") (pintype "passive"))
      (node (ref "R120") (pin "1") (pinfunction "1_1") (pintype "passive"))
      (node (ref "R122") (pin "1") (pinfunction "1_1") (pintype "passive"))
      (node (ref "R123") (pin "1") (pinfunction "1_1") (pintype "passive"))
      (node (ref "R127") (pin "1") (pinfunction "1_1") (pintype "passive"))
      (node (ref "R35") (pin "1") (pinfunction "1_1") (pintype "passive"))
      (node (ref "R41") (pin "1") (pinfunction "1_1") (pintype "passive"))
      (node (ref "SHLD3") (pin "1") (pinfunction "1_1") (pintype "passive"))
      (node (ref "U11") (pin "3") (pinfunction "C_3") (pintype "passive"))
      (node (ref "U11") (pin "4") (pinfunction "~{G2A}_4") (pintype "passive"))
      (node (ref "U11") (pin "5") (pinfunction "~{G2B}_5") (pintype "passive"))
      (node (ref "U11") (pin "8") (pinfunction "GND_8") (pintype "passive"))
      (node (ref "U7") (pin "17") (pinfunction "PAD_17") (pintype "power_in"))
      (node (ref "U7") (pin "5") (pinfunction "GND_5") (pintype "power_in"))
      (node (ref "U7") (pin "8") (pinfunction "GND_8") (pintype "power_in"))
      (node (ref "U8") (pin "1") (pinfunction "GND_1") (pintype "passive"))
      (node (ref "U8") (pin "14") (pinfunction "SDO/ADDR1_14") (pintype "passive"))
      (node (ref "U8") (pin "15") (pinfunction "INDEP_15") (pintype "passive"))
      (node (ref "U8") (pin "3") (pinfunction "W_3") (pintype "passive"))
      (node (ref "U8") (pin "4") (pinfunction "B_4") (pintype "passive"))
      (node (ref "U8") (pin "6") (pinfunction "~{SYNC}/ADDR0_6") (pintype "passive"))
      (node (ref "U9") (pin "17") (pinfunction "PAD_17") (pintype "passive"))
    )
    (net (code "30") (name "Net-(C20-Pad1)") (class "Default")
      (node (ref "C20") (pin "1") (pinfunction "1_1") (pintype "passive"))
      (node (ref "R30") (pin "1") (pinfunction "1_1") (pintype "passive"))
      (node (ref "R31") (pin "2") (pinfunction "2_2") (pintype "passive"))
    )
    (net (code "31") (name "Net-(C21-Pad1)") (class "Default")
      (node (ref "C21") (pin "1") (pinfunction "1_1") (pintype "passive"))
      (node (ref "C23") (pin "2") (pinfunction "2_2") (pintype "passive"))
      (node (ref "K1") (pin "7") (pinfunction "7_7") (pintype "passive"))
      (node (ref "R32") (pin "2") (pinfunction "2_2") (pintype "passive"))
      (node (ref "R35") (pin "2") (pinfunction "2_2") (pintype "passive"))
    )
    (net (code "32") (name "Net-(C21-Pad2)") (class "Default")
      (node (ref "C21") (pin "2") (pinfunction "2_2") (pintype "passive"))
      (node (ref "K1") (pin "2") (pinfunction "2_2") (pintype "passive"))
      (node (ref "R32") (pin "1") (pinfunction "1_1") (pintype "passive"))
    )
    (net (code "33") (name "Net-(C26-Pad2)") (class "Default")
      (node (ref "C26") (pin "2") (pinfunction "2_2") (pintype "passive"))
      (node (ref "R54") (pin "2") (pinfunction "2_2") (pintype "passive"))
    )
    (net (code "34") (name "Net-(J2-Signal)") (class "Default")
      (node (ref "J2") (pin "1") (pinfunction "Signal_1") (pintype "passive"))
      (node (ref "K2") (pin "3") (pinfunction "3_3") (pintype "passive"))
    )
    (net (code "35") (name "Net-(K1-Pad3)") (class "Default")
      (node (ref "K1") (pin "3") (pinfunction "3_3") (pintype "passive"))
      (node (ref "K2") (pin "6") (pinfunction "6_6") (pintype "passive"))
    )
    (net (code "36") (name "Net-(K1-Pad4)") (class "Default")
      (node (ref "K1") (pin "4") (pinfunction "4_4") (pintype "passive"))
      (node (ref "K1") (pin "5") (pinfunction "5_5") (pintype "passive"))
    )
    (net (code "37") (name "Net-(K2-Pad2)") (class "Default")
      (node (ref "K2") (pin "2") (pinfunction "2_2") (pintype "passive"))
      (node (ref "R31") (pin "1") (pinfunction "1_1") (pintype "passive"))
    )
    (net (code "38") (name "Net-(K2-Pad4)") (class "Default")
      (node (ref "K2") (pin "4") (pinfunction "4_4") (pintype "passive"))
      (node (ref "R29") (pin "1") (pinfunction "1_1") (pintype "passive"))
      (node (ref "R41") (pin "2") (pinfunction "2_2") (pintype "passive"))
    )
    (net (code "39") (name "Net-(K2-Pad5)") (class "Default")
      (node (ref "K2") (pin "5") (pinfunction "5_5") (pintype "passive"))
      (node (ref "R29") (pin "2") (pinfunction "2_2") (pintype "passive"))
    )
    (net (code "40") (name "Net-(K2-Pad7)") (class "Default")
      (node (ref "K2") (pin "7") (pinfunction "7_7") (pintype "passive"))
      (node (ref "R30") (pin "2") (pinfunction "2_2") (pintype "passive"))
    )
    (net (code "41") (name "Net-(Q5-G)") (class "Default")
      (node (ref "Q5") (pin "2") (pinfunction "G_2") (pintype "passive"))
      (node (ref "R126") (pin "1") (pinfunction "1_1") (pintype "passive"))
    )
    (net (code "42") (name "Net-(U7-IN_N)") (class "Default")
      (node (ref "C31") (pin "1") (pinfunction "1_1") (pintype "passive"))
      (node (ref "FB7") (pin "2") (pinfunction "2_2") (pintype "passive"))
      (node (ref "R118") (pin "1") (pinfunction "1_1") (pintype "passive"))
      (node (ref "R119") (pin "2") (pinfunction "2_2") (pintype "passive"))
      (node (ref "TP25") (pin "1") (pinfunction "1_1") (pintype "passive"))
      (node (ref "U7") (pin "7") (pinfunction "IN_N_7") (pintype "passive"))
    )
    (net (code "43") (name "Net-(U7-IN_P)") (class "Default")
      (node (ref "R56") (pin "2") (pinfunction "2_2") (pintype "passive"))
      (node (ref "U7") (pin "6") (pinfunction "IN_P_6") (pintype "passive"))
    )
    (net (code "44") (name "Net-(U8-A)") (class "Default")
      (node (ref "R121") (pin "1") (pinfunction "1_1") (pintype "passive"))
      (node (ref "R123") (pin "2") (pinfunction "2_2") (pintype "passive"))
      (node (ref "U8") (pin "2") (pinfunction "A_2") (pintype "passive"))
    )
    (net (code "45") (name "Net-(U9-CLL)") (class "Default")
      (node (ref "R120") (pin "2") (pinfunction "2_2") (pintype "passive"))
      (node (ref "U9") (pin "14") (pinfunction "CLL_14") (pintype "passive"))
    )
    (net (code "46") (name "Net-(U9-IN)") (class "Default")
      (node (ref "C26") (pin "1") (pinfunction "1_1") (pintype "passive"))
      (node (ref "R65") (pin "2") (pinfunction "2_2") (pintype "passive"))
      (node (ref "U9") (pin "2") (pinfunction "IN_2") (pintype "passive"))
    )
    (net (code "47") (name "Net-(U9-IN_Aux)") (class "Default")
      (node (ref "C29") (pin "2") (pinfunction "2_2") (pintype "passive"))
      (node (ref "R100") (pin "1") (pinfunction "1_1") (pintype "passive"))
      (node (ref "U9") (pin "4") (pinfunction "IN_Aux_4") (pintype "passive"))
    )
    (net (code "48") (name "Net-(U9-IN_Bias)") (class "Default")
      (node (ref "R65") (pin "1") (pinfunction "1_1") (pintype "passive"))
      (node (ref "U9") (pin "3") (pinfunction "IN_Bias_3") (pintype "passive"))
    )
    (net (code "49") (name "Net-(U9-OUT)") (class "Default")
      (node (ref "R56") (pin "1") (pinfunction "1_1") (pintype "passive"))
      (node (ref "R98") (pin "2") (pinfunction "2_2") (pintype "passive"))
      (node (ref "U9") (pin "11") (pinfunction "OUT_11") (pintype "passive"))
    )
    (net (code "50") (name "Net-(U9-R_Bias)") (class "Default")
      (node (ref "R55") (pin "1") (pinfunction "1_1") (pintype "passive"))
      (node (ref "U9") (pin "7") (pinfunction "R_Bias_7") (pintype "passive"))
    )
    (net (code "51") (name "Net-(U10-COM)") (class "Default")
      (node (ref "C27") (pin "2") (pinfunction "2_2") (pintype "passive"))
      (node (ref "R122") (pin "2") (pinfunction "2_2") (pintype "passive"))
      (node (ref "U10") (pin "1") (pinfunction "COM_1") (pintype "passive"))
      (node (ref "U18") (pin "3") (pinfunction "+_3") (pintype "passive"))
    )
    (net (code "52") (name "Net-(U10-NO)") (class "Default")
      (node (ref "C27") (pin "1") (pinfunction "1_1") (pintype "passive"))
      (node (ref "R96") (pin "1") (pinfunction "1_1") (pintype "passive"))
      (node (ref "U10") (pin "2") (pinfunction "NO_2") (pintype "passive"))
    )
    (net (code "53") (name "Net-(U11-Y0)") (class "Default")
      (node (ref "R17") (pin "1") (pinfunction "1_1") (pintype "passive"))
      (node (ref "U11") (pin "15") (pinfunction "Y0_15") (pintype "passive"))
    )
    (net (code "54") (name "Net-(U11-Y1)") (class "Default")
      (node (ref "R16") (pin "1") (pinfunction "1_1") (pintype "passive"))
      (node (ref "U11") (pin "14") (pinfunction "Y1_14") (pintype "passive"))
    )
    (net (code "55") (name "Net-(U11-Y2)") (class "Default")
      (node (ref "R15") (pin "1") (pinfunction "1_1") (pintype "passive"))
      (node (ref "U11") (pin "13") (pinfunction "Y2_13") (pintype "passive"))
    )
    (net (code "56") (name "Net-(U11-Y3)") (class "Default")
      (node (ref "R5") (pin "1") (pinfunction "1_1") (pintype "passive"))
      (node (ref "U11") (pin "12") (pinfunction "Y3_12") (pintype "passive"))
    )
    (net (code "57") (name "Net-(U18--)") (class "Default")
      (node (ref "C30") (pin "2") (pinfunction "2_2") (pintype "passive"))
      (node (ref "R121") (pin "2") (pinfunction "2_2") (pintype "passive"))
      (node (ref "R98") (pin "1") (pinfunction "1_1") (pintype "passive"))
      (node (ref "R99") (pin "2") (pinfunction "2_2") (pintype "passive"))
      (node (ref "U18") (pin "2") (pinfunction "-_2") (pintype "passive"))
    )
    (net (code "58") (name "Net-(U18-OUT)") (class "Default")
      (node (ref "C30") (pin "1") (pinfunction "1_1") (pintype "passive"))
      (node (ref "R100") (pin "2") (pinfunction "2_2") (pintype "passive"))
      (node (ref "U18") (pin "6") (pinfunction "OUT_6") (pintype "passive"))
    )
    (net (code "59") (name "unconnected-(U7-AUX_N-Pad2)") (class "Default")
      (node (ref "U7") (pin "2") (pinfunction "AUX_N_2") (pintype "passive+no_connect"))
    )
    (net (code "60") (name "unconnected-(U7-AUX_P-Pad1)") (class "Default")
      (node (ref "U7") (pin "1") (pinfunction "AUX_P_1") (pintype "passive+no_connect"))
    )
    (net (code "61") (name "unconnected-(U7-AUX_VCM-Pad16)") (class "Default")
      (node (ref "U7") (pin "16") (pinfunction "AUX_VCM_16") (pintype "input+no_connect"))
    )
    (net (code "62") (name "unconnected-(U8-EPAD-Pad17)") (class "Default")
      (node (ref "U8") (pin "17") (pinfunction "EPAD_17") (pintype "passive+no_connect"))
    )
    (net (code "63") (name "unconnected-(U9-NC-Pad9)") (class "Default")
      (node (ref "U9") (pin "9") (pinfunction "NC_9") (pintype "passive+no_connect"))
    )
    (net (code "64") (name "unconnected-(U9-NC-Pad13)") (class "Default")
      (node (ref "U9") (pin "13") (pinfunction "NC_13") (pintype "passive+no_connect"))
    )
    (net (code "65") (name "unconnected-(U9-NC-Pad16)") (class "Default")
      (node (ref "U9") (pin "16") (pinfunction "NC_16") (pintype "passive+no_connect"))
    )
    (net (code "66") (name "unconnected-(U11-Y4-Pad11)") (class "Default")
      (node (ref "U11") (pin "11") (pinfunction "Y4_11") (pintype "passive+no_connect"))
    )
    (net (code "67") (name "unconnected-(U11-Y5-Pad10)") (class "Default")
      (node (ref "U11") (pin "10") (pinfunction "Y5_10") (pintype "passive+no_connect"))
    )
    (net (code "68") (name "unconnected-(U11-Y6-Pad9)") (class "Default")
      (node (ref "U11") (pin "9") (pinfunction "Y6_9") (pintype "passive+no_connect"))
    )
    (net (code "69") (name "unconnected-(U11-Y7-Pad7)") (class "Default")
      (node (ref "U11") (pin "7") (pinfunction "Y7_7") (pintype "passive+no_connect"))
    )
    (net (code "70") (name "unconnected-(U18-N1-Pad1)") (class "Default")
      (node (ref "U18") (pin "1") (pinfunction "N1_1") (pintype "passive+no_connect"))
    )
    (net (code "71") (name "unconnected-(U18-N2-Pad8)") (class "Default")
      (node (ref "U18") (pin "8") (pinfunction "N2_8") (pintype "passive+no_connect"))
    )
  )
)
